# Power.net
KiCad netlist of a schematic drawn in Altium Designer
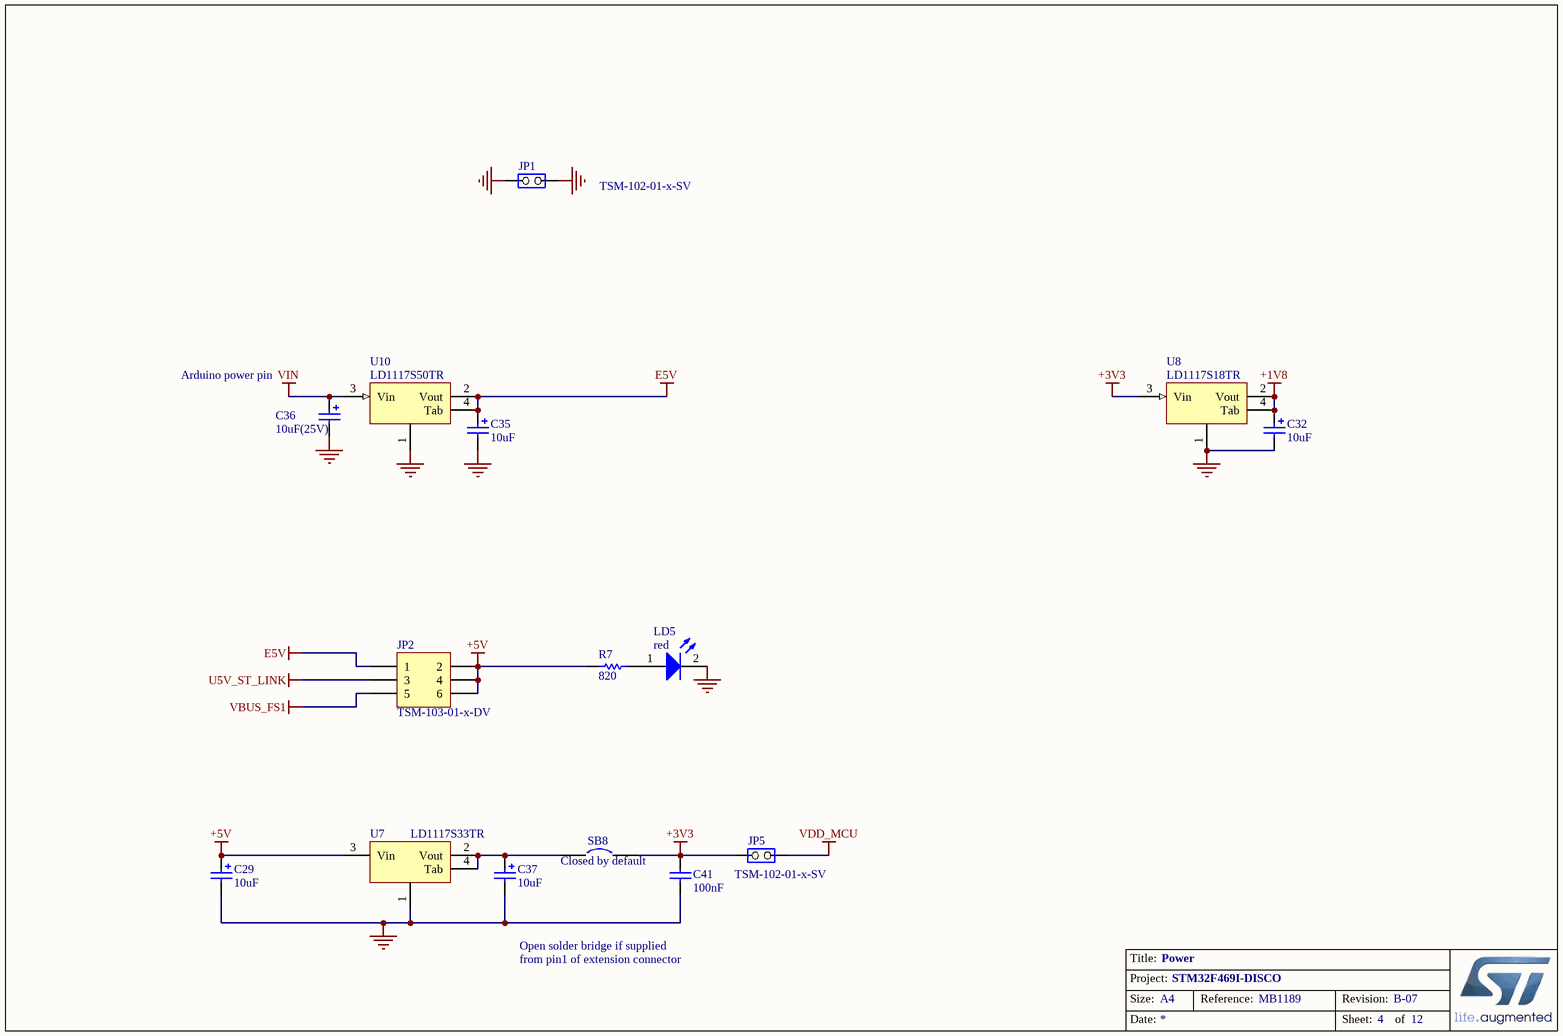
[diagram p0: Power.SchDoc]

(export (version "E")
  (design (tool "Eeschema 10.0.6"))
  (components
    (comp (ref "C29")
      (value "10uF")
      (footprint "TAN-A")
      (description "Polarized Capacitor (Radial)")
      (fields (field (name "PUBLISHER") "Altium Limited"))
      (libsource (lib "Miscellaneous Devices") (part "Cap Pol1"))
    )
    (comp (ref "C32")
      (value "10uF")
      (footprint "TAN-A")
      (description "Polarized Capacitor (Radial)")
      (fields (field (name "PUBLISHER") "Altium Limited"))
      (libsource (lib "Miscellaneous Devices") (part "Cap Pol1"))
    )
    (comp (ref "C35")
      (value "10uF")
      (footprint "TAN-A")
      (description "Polarized Capacitor (Radial)")
      (fields (field (name "PUBLISHER") "Altium Limited"))
      (libsource (lib "Miscellaneous Devices") (part "Cap Pol1"))
    )
    (comp (ref "C36")
      (value "10uF(25V)")
      (footprint "TAN-B")
      (description "Polarized Capacitor (Radial)")
      (fields (field (name "PUBLISHER") "Altium Limited"))
      (libsource (lib "Miscellaneous Devices") (part "Cap Pol1"))
    )
    (comp (ref "C37")
      (value "10uF")
      (footprint "TAN-A")
      (description "Polarized Capacitor (Radial)")
      (fields (field (name "PUBLISHER") "Altium Limited"))
      (libsource (lib "Miscellaneous Devices") (part "Cap Pol1"))
    )
    (comp (ref "C41")
      (value "100nF")
      (footprint "0402C")
      (description "Capacitor")
      (fields (field (name "PUBLISHER") "Altium Limited"))
      (libsource (lib "Miscellaneous Devices") (part "Cap"))
    )
    (comp (ref "JP1")
      (value "TSM-102-01-x-SV")
      (footprint "TSM-102-01-x-SV")
      (libsource (lib "*") (part "JP2"))
    )
    (comp (ref "JP2")
      (value "TSM-103-01-x-DV")
      (footprint "TSM-103-01-x-DV")
      (description "Header, 3-Pin, Dual row")
      (fields (field (name "PUBLISHER") "Altium Limited"))
      (libsource (lib "Miscellaneous Connectors") (part "Header 3X2"))
    )
    (comp (ref "JP5")
      (value "TSM-102-01-x-SV")
      (footprint "TSM-102-01-x-SV")
      (libsource (lib "*") (part "JP2"))
    )
    (comp (ref "LD5")
      (value "red")
      (footprint "0603D")
      (description "Typical RED, GREEN, YELLOW, AMBER GaAs LED")
      (fields (field (name "PUBLISHER") "Altium Limited"))
      (libsource (lib "Miscellaneous Devices") (part "LED2"))
    )
    (comp (ref "R7")
      (value "820")
      (footprint "0603R")
      (description "Resistor")
      (fields (field (name "PUBLISHER") "Altium Limited"))
      (libsource (lib "Miscellaneous Devices") (part "res1"))
    )
    (comp (ref "SB8")
      (value "Closed by default")
      (footprint "SB_0603")
      (description "Circuit Breaker")
      (fields (field (name "PUBLISHER") "Altium Limited"))
      (libsource (lib "Miscellaneous Devices") (part "Circuit Breaker"))
    )
    (comp (ref "U7")
      (value "LD1117S33TR")
      (footprint "SOT-223")
      (description "LOW DROP FIXED AND ADJUSTABLE POSITIVE VOLTAGE REGULATORS (3.3 Volts)")
      (libsource (lib "MCD_TOOLS") (part "LD1117S33TR"))
    )
    (comp (ref "U8") (value "LD1117S18TR") (footprint "SOT-223") (libsource (lib "mb1045") (part "LD1117")))
    (comp (ref "U10") (value "LD1117S50TR") (footprint "SOT-223") (libsource (lib "mb1045") (part "LD1117")))
  )
  (nets
    (net (code "1") (name "+1V8") (class "Default")
      (node (ref "C32") (pin "1") (pinfunction "1_1") (pintype "passive"))
      (node (ref "U8") (pin "2") (pinfunction "Vout_2") (pintype "power_in"))
      (node (ref "U8") (pin "4") (pinfunction "Tab_4") (pintype "power_in"))
    )
    (net (code "2") (name "+3V3") (class "Default")
      (node (ref "C41") (pin "1") (pinfunction "1_1") (pintype "passive"))
      (node (ref "JP5") (pin "1") (pinfunction "COMMON_1") (pintype "passive"))
      (node (ref "SB8") (pin "2") (pinfunction "2_2") (pintype "passive"))
      (node (ref "U8") (pin "3") (pinfunction "Vin_3") (pintype "input"))
    )
    (net (code "3") (name "+5V") (class "Default")
      (node (ref "C29") (pin "1") (pinfunction "1_1") (pintype "passive"))
      (node (ref "JP2") (pin "2") (pinfunction "2_2") (pintype "passive"))
      (node (ref "JP2") (pin "4") (pinfunction "4_4") (pintype "passive"))
      (node (ref "JP2") (pin "6") (pinfunction "6_6") (pintype "passive"))
      (node (ref "R7") (pin "2") (pinfunction "2_2") (pintype "passive"))
      (node (ref "U7") (pin "3") (pinfunction "Vin_3") (pintype "passive"))
    )
    (net (code "4") (name "E5V") (class "Default")
      (node (ref "C35") (pin "1") (pinfunction "1_1") (pintype "passive"))
      (node (ref "JP2") (pin "1") (pinfunction "1_1") (pintype "passive"))
      (node (ref "U10") (pin "2") (pinfunction "Vout_2") (pintype "power_in"))
      (node (ref "U10") (pin "4") (pinfunction "Tab_4") (pintype "power_in"))
    )
    (net (code "5") (name "GND") (class "Default")
      (node (ref "C29") (pin "2") (pinfunction "2_2") (pintype "passive"))
      (node (ref "C32") (pin "2") (pinfunction "2_2") (pintype "passive"))
      (node (ref "C35") (pin "2") (pinfunction "2_2") (pintype "passive"))
      (node (ref "C36") (pin "2") (pinfunction "2_2") (pintype "passive"))
      (node (ref "C37") (pin "2") (pinfunction "2_2") (pintype "passive"))
      (node (ref "C41") (pin "2") (pinfunction "2_2") (pintype "passive"))
      (node (ref "JP1") (pin "1") (pinfunction "COMMON_1") (pintype "passive"))
      (node (ref "JP1") (pin "2") (pinfunction "NO_2") (pintype "passive"))
      (node (ref "LD5") (pin "2") (pinfunction "K_2") (pintype "passive"))
      (node (ref "U10") (pin "1") (pintype "passive"))
      (node (ref "U7") (pin "1") (pintype "passive"))
      (node (ref "U8") (pin "1") (pintype "passive"))
    )
    (net (code "6") (name "Net-(LD5-A)") (class "Default")
      (node (ref "LD5") (pin "1") (pinfunction "A_1") (pintype "passive"))
      (node (ref "R7") (pin "1") (pinfunction "1_1") (pintype "passive"))
    )
    (net (code "7") (name "Net-(U7-Tab)") (class "Default")
      (node (ref "C37") (pin "1") (pinfunction "1_1") (pintype "passive"))
      (node (ref "SB8") (pin "1") (pinfunction "1_1") (pintype "passive"))
      (node (ref "U7") (pin "2") (pinfunction "Vout_2") (pintype "passive"))
      (node (ref "U7") (pin "4") (pinfunction "Tab_4") (pintype "passive"))
    )
    (net (code "8") (name "U5V_ST_LINK") (class "Default")
      (node (ref "JP2") (pin "3") (pinfunction "3_3") (pintype "passive"))
    )
    (net (code "9") (name "VBUS_FS1") (class "Default")
      (node (ref "JP2") (pin "5") (pinfunction "5_5") (pintype "passive"))
    )
    (net (code "10") (name "VDD_MCU") (class "Default")
      (node (ref "JP5") (pin "2") (pinfunction "NO_2") (pintype "passive"))
    )
    (net (code "11") (name "VIN") (class "Default")
      (node (ref "C36") (pin "1") (pinfunction "1_1") (pintype "passive"))
      (node (ref "U10") (pin "3") (pinfunction "Vin_3") (pintype "input"))
    )
  )
)
